# 10-RGB.net
KiCad netlist of a schematic drawn in Altium Designer
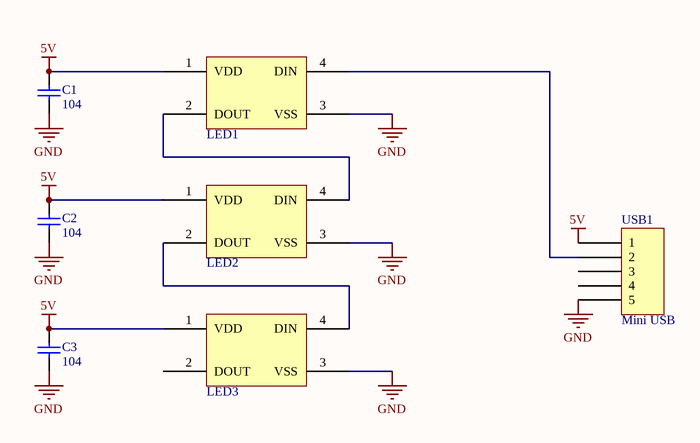
[diagram p0: 10-RGB模块原理图.SchDoc]

(export (version "E")
  (design (tool "Eeschema 10.0.6"))
  (components
    (comp (ref "C1")
      (value "104")
      (footprint "0603")
      (description "Capacitor")
      (fields (field (name "Comment") "Cap") (field (name "PUBLISHER") "Altium Limited"))
      (libsource (lib "Miscellaneous Devices") (part "Cap"))
    )
    (comp (ref "C2")
      (value "104")
      (footprint "0603")
      (description "Capacitor")
      (fields (field (name "Comment") "Cap") (field (name "PUBLISHER") "Altium Limited"))
      (libsource (lib "Miscellaneous Devices") (part "Cap"))
    )
    (comp (ref "C3")
      (value "104")
      (footprint "0603")
      (description "Capacitor")
      (fields (field (name "Comment") "Cap") (field (name "PUBLISHER") "Altium Limited"))
      (libsource (lib "Miscellaneous Devices") (part "Cap"))
    )
    (comp (ref "LED1") (value "RGB WS2811") (footprint "RGB") (libsource (lib "Schlib1") (part "RGB WS2811")))
    (comp (ref "LED2") (value "RGB WS2811") (footprint "RGB") (libsource (lib "Schlib1") (part "RGB WS2811")))
    (comp (ref "LED3") (value "RGB WS2811") (footprint "RGB") (libsource (lib "Schlib1") (part "RGB WS2811")))
    (comp (ref "USB1")
      (value "Mini USB")
      (footprint "USB/SM0.8-6H5")
      (libsource (lib "Schlib1") (part "Mini USB"))
    )
  )
  (nets
    (net (code "1") (name "5V") (class "Default")
      (node (ref "C1") (pin "2") (pinfunction "2_2") (pintype "passive"))
      (node (ref "C2") (pin "2") (pinfunction "2_2") (pintype "passive"))
      (node (ref "C3") (pin "2") (pinfunction "2_2") (pintype "passive"))
      (node (ref "LED1") (pin "1") (pinfunction "VDD_1") (pintype "passive"))
      (node (ref "LED2") (pin "1") (pinfunction "VDD_1") (pintype "passive"))
      (node (ref "LED3") (pin "1") (pinfunction "VDD_1") (pintype "passive"))
      (node (ref "USB1") (pin "1") (pinfunction "1_1") (pintype "passive"))
    )
    (net (code "2") (name "GND") (class "Default")
      (node (ref "C1") (pin "1") (pinfunction "1_1") (pintype "passive"))
      (node (ref "C2") (pin "1") (pinfunction "1_1") (pintype "passive"))
      (node (ref "C3") (pin "1") (pinfunction "1_1") (pintype "passive"))
      (node (ref "LED1") (pin "3") (pinfunction "VSS_3") (pintype "passive"))
      (node (ref "LED2") (pin "3") (pinfunction "VSS_3") (pintype "passive"))
      (node (ref "LED3") (pin "3") (pinfunction "VSS_3") (pintype "passive"))
      (node (ref "USB1") (pin "5") (pinfunction "5_5") (pintype "passive"))
    )
    (net (code "3") (name "Net-(LED1-DIN)") (class "Default")
      (node (ref "LED1") (pin "4") (pinfunction "DIN_4") (pintype "passive"))
      (node (ref "USB1") (pin "2") (pinfunction "2_2") (pintype "passive"))
    )
    (net (code "4") (name "Net-(LED1-DOUT)") (class "Default")
      (node (ref "LED1") (pin "2") (pinfunction "DOUT_2") (pintype "passive"))
      (node (ref "LED2") (pin "4") (pinfunction "DIN_4") (pintype "passive"))
    )
    (net (code "5") (name "Net-(LED2-DOUT)") (class "Default")
      (node (ref "LED2") (pin "2") (pinfunction "DOUT_2") (pintype "passive"))
      (node (ref "LED3") (pin "4") (pinfunction "DIN_4") (pintype "passive"))
    )
    (net (code "6") (name "unconnected-(LED3-DOUT-Pad2)") (class "Default")
      (node (ref "LED3") (pin "2") (pinfunction "DOUT_2") (pintype "passive"))
    )
    (net (code "7") (name "unconnected-(USB1-Pad3)") (class "Default")
      (node (ref "USB1") (pin "3") (pinfunction "3_3") (pintype "passive"))
    )
    (net (code "8") (name "unconnected-(USB1-Pad4)") (class "Default")
      (node (ref "USB1") (pin "4") (pinfunction "4_4") (pintype "passive"))
    )
  )
)
